# schem.net
KiCad netlist of a schematic drawn in EasyEDA
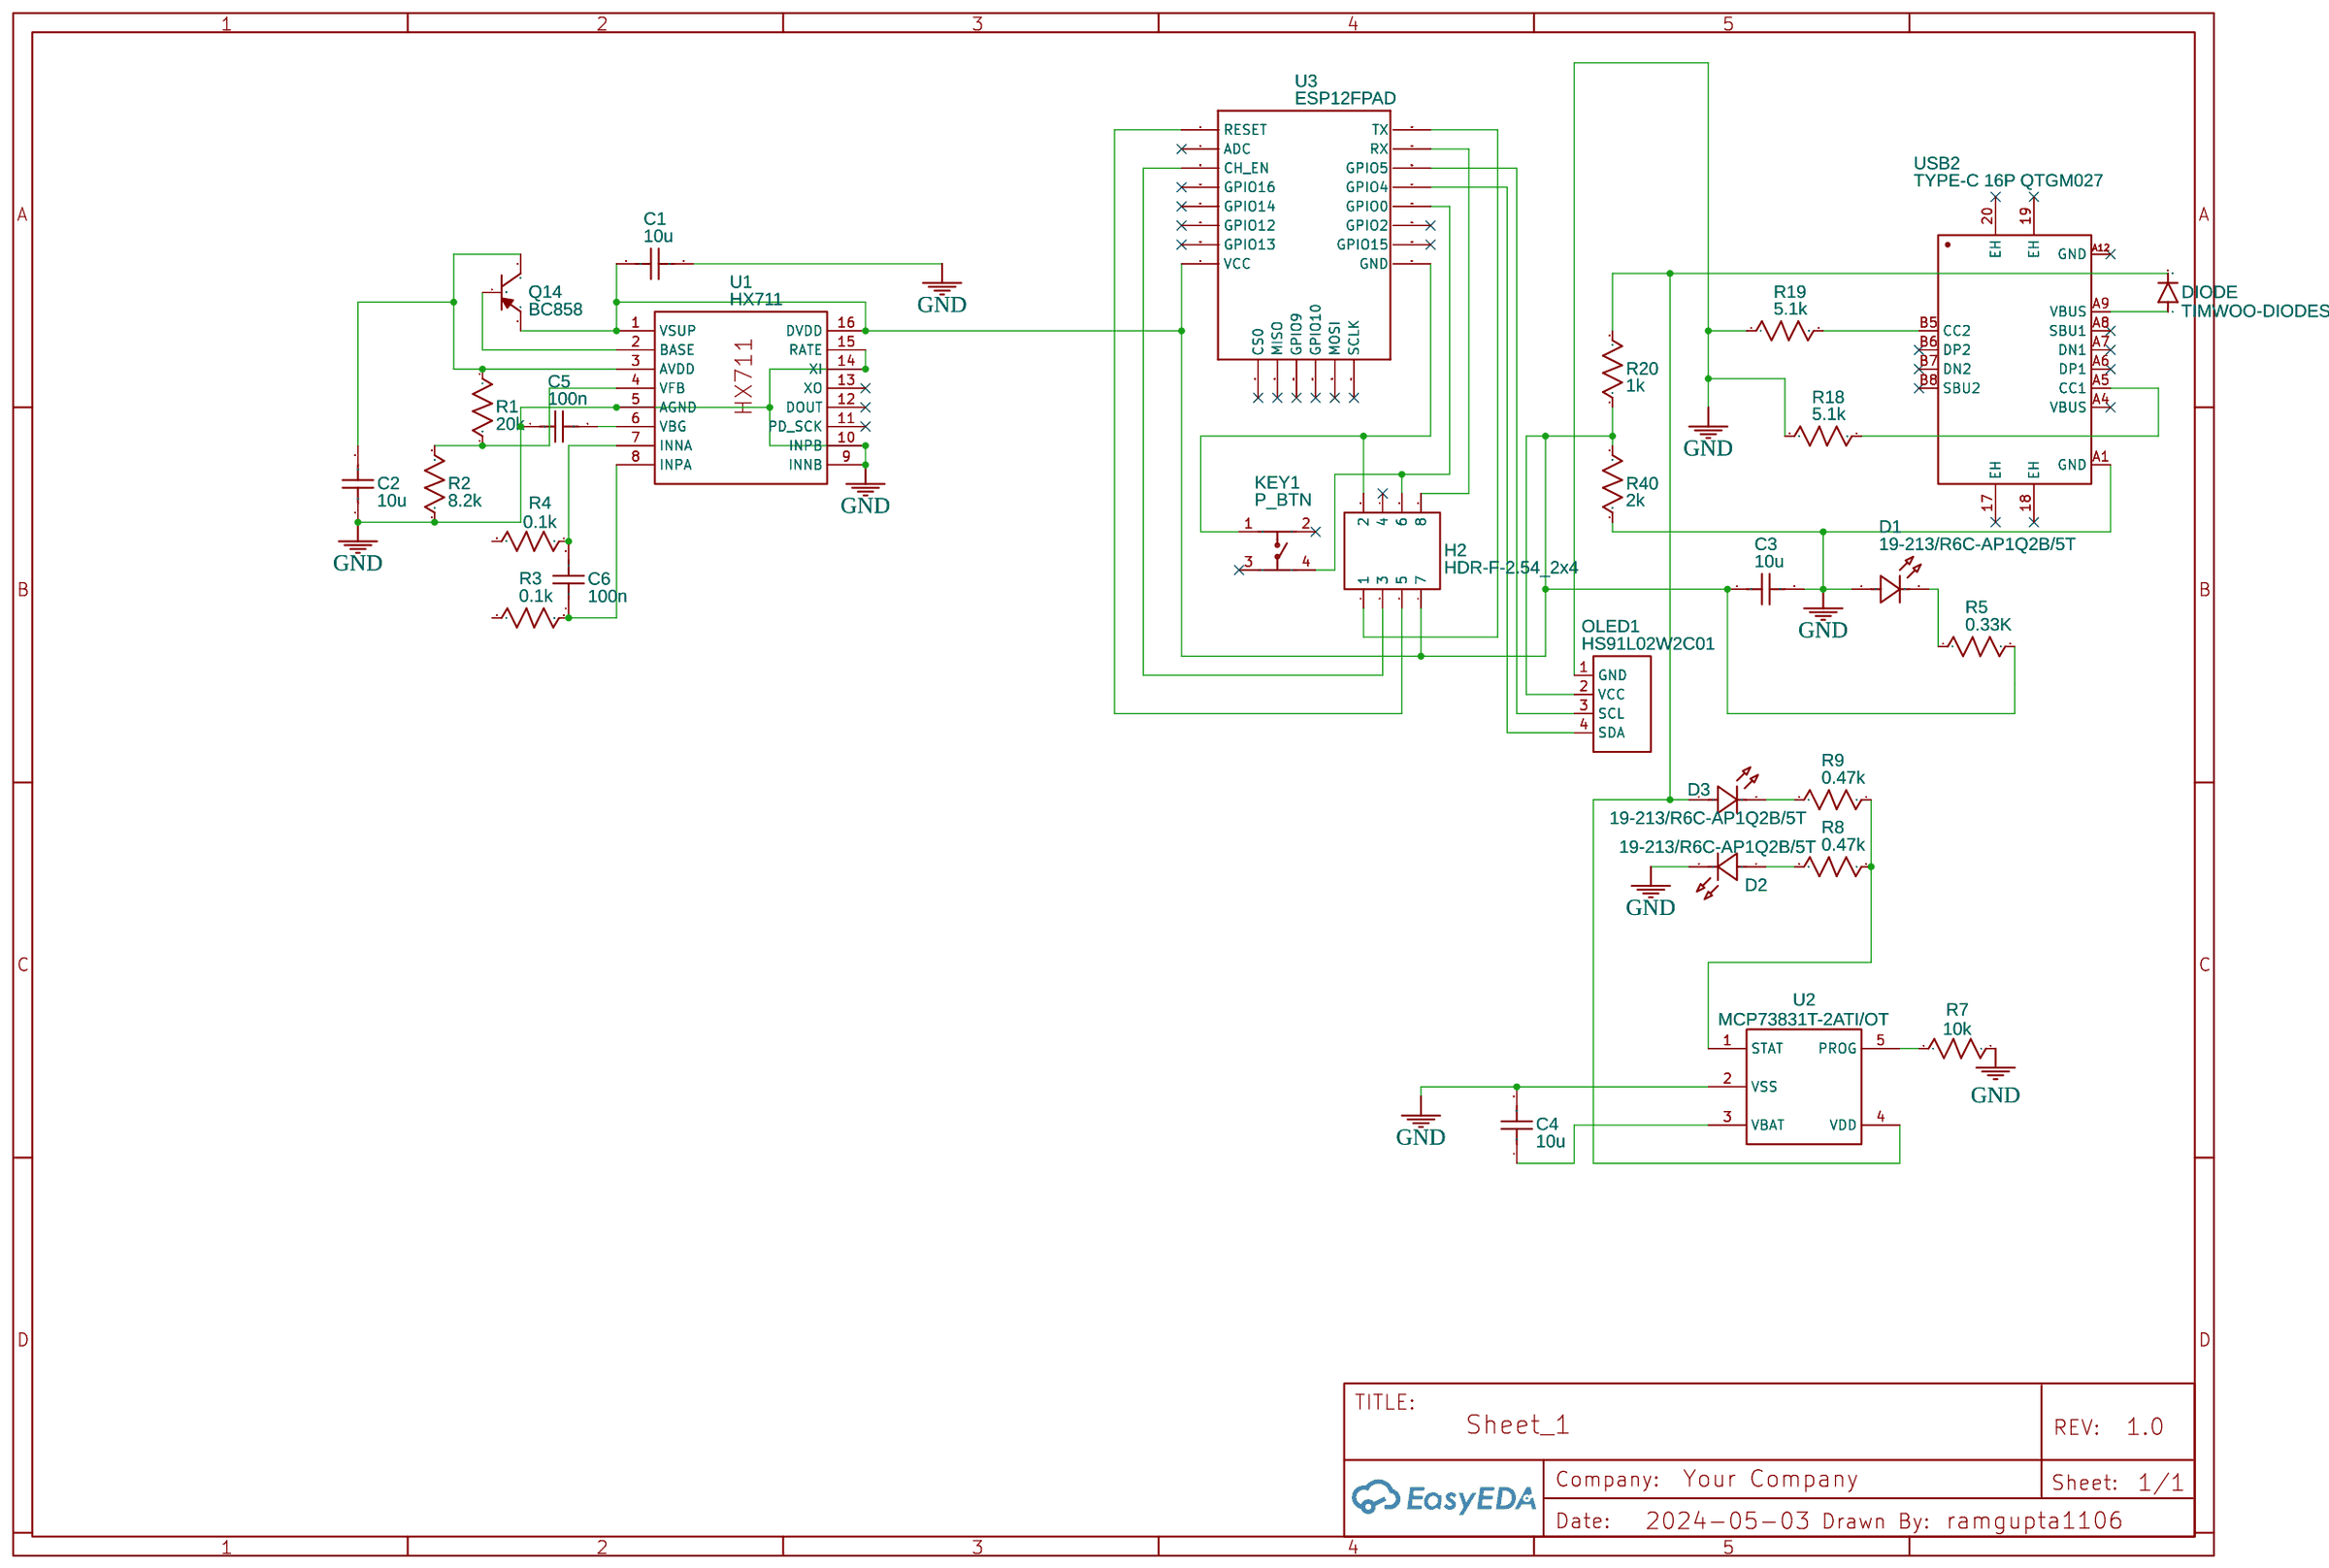
[diagram p0: schematic sheet]

(export (version "E")
  (design (tool "Eeschema 10.0.6"))
  (components
    (comp (ref "C1") (value "10u") (libsource (lib "") (part "C_0603_US")))
    (comp (ref "C2") (value "10u") (libsource (lib "") (part "C_0603_US_1")))
    (comp (ref "C3") (value "10u") (libsource (lib "") (part "C_0603_US")))
    (comp (ref "C4") (value "10u") (libsource (lib "") (part "C_0603_US_1")))
    (comp (ref "C5") (value "100n") (libsource (lib "") (part "C_0603_US")))
    (comp (ref "C6") (value "100n") (libsource (lib "") (part "C_0603_US_1")))
    (comp (ref "D1")
      (value "19-213/R6C-AP1Q2B/5T")
      (fields (field (name "Manufacturer") "EVERLIGHT(亿光)"))
      (libsource (lib "") (part "19-213/R6C-AP1Q2B/5T"))
    )
    (comp (ref "D2")
      (value "19-213/R6C-AP1Q2B/5T")
      (fields (field (name "Manufacturer") "EVERLIGHT(亿光)"))
      (libsource (lib "") (part "19-213/R6C-AP1Q2B/5T_1"))
    )
    (comp (ref "D3")
      (value "19-213/R6C-AP1Q2B/5T")
      (fields (field (name "Manufacturer") "EVERLIGHT(亿光)"))
      (libsource (lib "") (part "19-213/R6C-AP1Q2B/5T"))
    )
    (comp (ref "DIODE") (value "TIMWOO-DIODES_DIODEHV") (libsource (lib "") (part "TIMWOO-DIODES_DIODEHV")))
    (comp (ref "H2") (value "HDR-F-2.54_2x4") (libsource (lib "") (part "HDR-F-2.54_2x4")))
    (comp (ref "KEY1")
      (value "P_BTN")
      (fields (field (name "Manufacturer Part") "4pinTACTPCBTHTPushButton"))
      (libsource (lib "") (part "4PINTACTPCBTHTPUSHBUTTON"))
    )
    (comp (ref "OLED1")
      (value "HS91L02W2C01")
      (fields (field (name "Manufacturer") "HS(汉昇)"))
      (libsource (lib "") (part "HS91L02W2C01"))
    )
    (comp (ref "Q14")
      (value "BC858")
      (fields (field (name "Manufacturer") "HT(Shenzhen Jinyu Semicon)"))
      (libsource (lib "") (part "BC858"))
    )
    (comp (ref "R1") (value "20k") (libsource (lib "") (part "R_0603_US_3")))
    (comp (ref "R2") (value "8.2k") (libsource (lib "") (part "R_0603_US_1")))
    (comp (ref "R3") (value "0.1k") (libsource (lib "") (part "R_0603_US")))
    (comp (ref "R4") (value "0.1k") (libsource (lib "") (part "R_0603_US_2")))
    (comp (ref "R5") (value "0.33K") (libsource (lib "") (part "R_0603_US")))
    (comp (ref "R7") (value "10k") (libsource (lib "") (part "R_0603_US")))
    (comp (ref "R8") (value "0.47k") (libsource (lib "") (part "R_0603_US")))
    (comp (ref "R9") (value "0.47k") (libsource (lib "") (part "R_0603_US")))
    (comp (ref "R18") (value "5.1k") (libsource (lib "") (part "R_0603_US")))
    (comp (ref "R19") (value "5.1k") (libsource (lib "") (part "R_0603_US")))
    (comp (ref "R20") (value "1k") (libsource (lib "") (part "R_0603_US_1")))
    (comp (ref "R40") (value "2k") (libsource (lib "") (part "R_0603_US_1")))
    (comp (ref "U1")
      (value "HX711")
      (fields (field (name "Manufacturer") "AVIA(海芯科技)"))
      (libsource (lib "") (part "HX711"))
    )
    (comp (ref "U2")
      (value "MCP73831T-2ATI/OT")
      (fields (field (name "Manufacturer") "MICROCHIP(美国微芯)"))
      (libsource (lib "") (part "MCP73831T-2ATI/OT"))
    )
    (comp (ref "U3") (value "ESP12FPAD") (libsource (lib "") (part "ESP12FPAD")))
    (comp (ref "USB2")
      (value "TYPE-C 16P QTGM027")
      (fields (field (name "Manufacturer") "SHOU HAN(首韩)"))
      (libsource (lib "") (part "TYPE-C 16P QTGM027"))
    )
  )
  (nets
    (net (code "1") (name "GND") (class "Default")
      (node (ref "C1") (pin "2") (pinfunction "2_2") (pintype "unspecified"))
      (node (ref "C2") (pin "1") (pinfunction "1_1") (pintype "unspecified"))
      (node (ref "C3") (pin "2") (pinfunction "2_2") (pintype "unspecified"))
      (node (ref "C4") (pin "2") (pinfunction "2_2") (pintype "unspecified"))
      (node (ref "C5") (pin "1") (pinfunction "1_1") (pintype "unspecified"))
      (node (ref "D1") (pin "1") (pinfunction "A_1") (pintype "unspecified"))
      (node (ref "D2") (pin "2") (pinfunction "K_2") (pintype "unspecified"))
      (node (ref "OLED1") (pin "1") (pinfunction "GND_1") (pintype "unspecified"))
      (node (ref "R18") (pin "1") (pinfunction "1_1") (pintype "unspecified"))
      (node (ref "R19") (pin "1") (pinfunction "1_1") (pintype "unspecified"))
      (node (ref "R2") (pin "1") (pinfunction "1_1") (pintype "unspecified"))
      (node (ref "R40") (pin "1") (pinfunction "1_1") (pintype "unspecified"))
      (node (ref "R7") (pin "2") (pinfunction "2_2") (pintype "unspecified"))
      (node (ref "U1") (pin "10") (pinfunction "INPB_10") (pintype "unspecified"))
      (node (ref "U1") (pin "14") (pinfunction "XI_14") (pintype "unspecified"))
      (node (ref "U1") (pin "15") (pinfunction "RATE_15") (pintype "unspecified"))
      (node (ref "U1") (pin "5") (pinfunction "AGND_5") (pintype "unspecified"))
      (node (ref "U1") (pin "9") (pinfunction "INNB_9") (pintype "unspecified"))
      (node (ref "U2") (pin "2") (pinfunction "VSS_2") (pintype "unspecified"))
      (node (ref "USB2") (pin "A1") (pinfunction "GND_A1") (pintype "unspecified"))
    )
    (net (code "2") (name "Net-(D1-K)") (class "Default")
      (node (ref "D1") (pin "2") (pinfunction "K_2") (pintype "unspecified"))
      (node (ref "R5") (pin "1") (pinfunction "1_1") (pintype "unspecified"))
    )
    (net (code "3") (name "Net-(D2-A)") (class "Default")
      (node (ref "D2") (pin "1") (pinfunction "A_1") (pintype "unspecified"))
      (node (ref "R8") (pin "1") (pinfunction "1_1") (pintype "unspecified"))
    )
    (net (code "4") (name "Net-(D3-A)") (class "Default")
      (node (ref "D3") (pin "1") (pinfunction "A_1") (pintype "unspecified"))
      (node (ref "DIODE") (pin "C") (pinfunction "C_C") (pintype "bidirectional"))
      (node (ref "R20") (pin "2") (pinfunction "2_2") (pintype "unspecified"))
      (node (ref "U2") (pin "4") (pinfunction "VDD_4") (pintype "unspecified"))
    )
    (net (code "5") (name "Net-(D3-K)") (class "Default")
      (node (ref "D3") (pin "2") (pinfunction "K_2") (pintype "unspecified"))
      (node (ref "R9") (pin "1") (pinfunction "1_1") (pintype "unspecified"))
    )
    (net (code "6") (name "Net-(DIODE-PadA)") (class "Default")
      (node (ref "DIODE") (pin "A") (pinfunction "A_A") (pintype "bidirectional"))
      (node (ref "USB2") (pin "A9") (pinfunction "VBUS_A9") (pintype "unspecified"))
    )
    (net (code "7") (name "Net-(H2-Pad2)") (class "Default")
      (node (ref "H2") (pin "2") (pinfunction "2_2") (pintype "unspecified"))
      (node (ref "KEY1") (pin "1") (pinfunction "1_1") (pintype "unspecified"))
      (node (ref "U3") (pin "GND") (pinfunction "GND_GND") (pintype "bidirectional"))
    )
    (net (code "8") (name "Net-(H2-Pad5)") (class "Default")
      (node (ref "H2") (pin "5") (pinfunction "5_5") (pintype "unspecified"))
      (node (ref "U3") (pin "RESET") (pinfunction "RESET_RESET") (pintype "bidirectional"))
    )
    (net (code "9") (name "Net-(H2-Pad6)") (class "Default")
      (node (ref "H2") (pin "6") (pinfunction "6_6") (pintype "unspecified"))
      (node (ref "KEY1") (pin "4") (pinfunction "4_4") (pintype "unspecified"))
      (node (ref "U3") (pin "GPIO0") (pinfunction "GPIO0_GPIO0") (pintype "bidirectional"))
    )
    (net (code "10") (name "Net-(OLED1-SCL)") (class "Default")
      (node (ref "OLED1") (pin "3") (pinfunction "SCL_3") (pintype "unspecified"))
      (node (ref "U3") (pin "GPIO5") (pinfunction "GPIO5_GPIO5") (pintype "bidirectional"))
    )
    (net (code "11") (name "Net-(OLED1-SDA)") (class "Default")
      (node (ref "OLED1") (pin "4") (pinfunction "SDA_4") (pintype "unspecified"))
      (node (ref "U3") (pin "GPIO4") (pinfunction "GPIO4_GPIO4") (pintype "bidirectional"))
    )
    (net (code "12") (name "Net-(OLED1-VCC)") (class "Default")
      (node (ref "C1") (pin "1") (pinfunction "1_1") (pintype "unspecified"))
      (node (ref "C3") (pin "1") (pinfunction "1_1") (pintype "unspecified"))
      (node (ref "H2") (pin "7") (pinfunction "7_7") (pintype "unspecified"))
      (node (ref "OLED1") (pin "2") (pinfunction "VCC_2") (pintype "unspecified"))
      (node (ref "Q14") (pin "2") (pinfunction "E_2") (pintype "input"))
      (node (ref "R20") (pin "1") (pinfunction "1_1") (pintype "unspecified"))
      (node (ref "R40") (pin "2") (pinfunction "2_2") (pintype "unspecified"))
      (node (ref "R5") (pin "2") (pinfunction "2_2") (pintype "unspecified"))
      (node (ref "U1") (pin "1") (pinfunction "VSUP_1") (pintype "unspecified"))
      (node (ref "U1") (pin "16") (pinfunction "DVDD_16") (pintype "unspecified"))
      (node (ref "U3") (pin "VCC") (pinfunction "VCC_VCC") (pintype "bidirectional"))
    )
    (net (code "13") (name "Net-(Q14-B)") (class "Default")
      (node (ref "Q14") (pin "1") (pinfunction "B_1") (pintype "input"))
      (node (ref "U1") (pin "2") (pinfunction "BASE_2") (pintype "unspecified"))
    )
    (net (code "14") (name "Net-(Q14-C)") (class "Default")
      (node (ref "C2") (pin "2") (pinfunction "2_2") (pintype "unspecified"))
      (node (ref "Q14") (pin "3") (pinfunction "C_3") (pintype "input"))
      (node (ref "R1") (pin "1") (pinfunction "1_1") (pintype "unspecified"))
      (node (ref "U1") (pin "3") (pinfunction "AVDD_3") (pintype "unspecified"))
    )
    (net (code "15") (name "Net-(U1-INNA)") (class "Default")
      (node (ref "C6") (pin "2") (pinfunction "2_2") (pintype "unspecified"))
      (node (ref "R4") (pin "1") (pinfunction "1_1") (pintype "unspecified"))
      (node (ref "U1") (pin "7") (pinfunction "INNA_7") (pintype "unspecified"))
    )
    (net (code "16") (name "Net-(U1-INPA)") (class "Default")
      (node (ref "C6") (pin "1") (pinfunction "1_1") (pintype "unspecified"))
      (node (ref "R3") (pin "2") (pinfunction "2_2") (pintype "unspecified"))
      (node (ref "U1") (pin "8") (pinfunction "INPA_8") (pintype "unspecified"))
    )
    (net (code "17") (name "Net-(U1-VBG)") (class "Default")
      (node (ref "C5") (pin "2") (pinfunction "2_2") (pintype "unspecified"))
      (node (ref "U1") (pin "6") (pinfunction "VBG_6") (pintype "unspecified"))
    )
    (net (code "18") (name "Net-(U1-VFB)") (class "Default")
      (node (ref "R1") (pin "2") (pinfunction "2_2") (pintype "unspecified"))
      (node (ref "R2") (pin "2") (pinfunction "2_2") (pintype "unspecified"))
      (node (ref "U1") (pin "4") (pinfunction "VFB_4") (pintype "unspecified"))
    )
    (net (code "19") (name "Net-(U2-PROG)") (class "Default")
      (node (ref "R7") (pin "1") (pinfunction "1_1") (pintype "unspecified"))
      (node (ref "U2") (pin "5") (pinfunction "PROG_5") (pintype "unspecified"))
    )
    (net (code "20") (name "Net-(U2-STAT)") (class "Default")
      (node (ref "R8") (pin "2") (pinfunction "2_2") (pintype "unspecified"))
      (node (ref "R9") (pin "2") (pinfunction "2_2") (pintype "unspecified"))
      (node (ref "U2") (pin "1") (pinfunction "STAT_1") (pintype "unspecified"))
    )
    (net (code "21") (name "Net-(U2-VBAT)") (class "Default")
      (node (ref "C4") (pin "1") (pinfunction "1_1") (pintype "unspecified"))
      (node (ref "U2") (pin "3") (pinfunction "VBAT_3") (pintype "unspecified"))
    )
    (net (code "22") (name "Net-(U3-CH_EN)") (class "Default")
      (node (ref "H2") (pin "3") (pinfunction "3_3") (pintype "unspecified"))
      (node (ref "U3") (pin "CH_PD") (pinfunction "CH_EN_CH_PD") (pintype "bidirectional"))
    )
    (net (code "23") (name "Net-(U3-RX)") (class "Default")
      (node (ref "H2") (pin "8") (pinfunction "8_8") (pintype "unspecified"))
      (node (ref "U3") (pin "RXD0") (pinfunction "RX_RXD0") (pintype "bidirectional"))
    )
    (net (code "24") (name "Net-(U3-TX)") (class "Default")
      (node (ref "H2") (pin "1") (pinfunction "1_1") (pintype "unspecified"))
      (node (ref "U3") (pin "TXD0") (pinfunction "TX_TXD0") (pintype "bidirectional"))
    )
    (net (code "25") (name "Net-(USB2-CC1)") (class "Default")
      (node (ref "R18") (pin "2") (pinfunction "2_2") (pintype "unspecified"))
      (node (ref "USB2") (pin "A5") (pinfunction "CC1_A5") (pintype "unspecified"))
    )
    (net (code "26") (name "Net-(USB2-CC2)") (class "Default")
      (node (ref "R19") (pin "2") (pinfunction "2_2") (pintype "unspecified"))
      (node (ref "USB2") (pin "B5") (pinfunction "CC2_B5") (pintype "unspecified"))
    )
    (net (code "27") (name "unconnected-(H2-Pad4)") (class "Default")
      (node (ref "H2") (pin "4") (pinfunction "4_4") (pintype "unspecified+no_connect"))
    )
    (net (code "28") (name "unconnected-(KEY1-Pad2)") (class "Default")
      (node (ref "KEY1") (pin "2") (pinfunction "2_2") (pintype "unspecified+no_connect"))
    )
    (net (code "29") (name "unconnected-(KEY1-Pad3)") (class "Default")
      (node (ref "KEY1") (pin "3") (pinfunction "3_3") (pintype "unspecified+no_connect"))
    )
    (net (code "30") (name "unconnected-(R3-Pad1)") (class "Default")
      (node (ref "R3") (pin "1") (pinfunction "1_1") (pintype "unspecified"))
    )
    (net (code "31") (name "unconnected-(R4-Pad2)") (class "Default")
      (node (ref "R4") (pin "2") (pinfunction "2_2") (pintype "unspecified"))
    )
    (net (code "32") (name "unconnected-(U1-DOUT-Pad12)") (class "Default")
      (node (ref "U1") (pin "12") (pinfunction "DOUT_12") (pintype "unspecified+no_connect"))
    )
    (net (code "33") (name "unconnected-(U1-PD_SCK-Pad11)") (class "Default")
      (node (ref "U1") (pin "11") (pinfunction "PD_SCK_11") (pintype "unspecified+no_connect"))
    )
    (net (code "34") (name "unconnected-(U1-XO-Pad13)") (class "Default")
      (node (ref "U1") (pin "13") (pinfunction "XO_13") (pintype "unspecified+no_connect"))
    )
    (net (code "35") (name "unconnected-(U3-PadADC)") (class "Default")
      (node (ref "U3") (pin "ADC") (pinfunction "ADC_ADC") (pintype "bidirectional+no_connect"))
    )
    (net (code "36") (name "unconnected-(U3-PadCS0)") (class "Default")
      (node (ref "U3") (pin "CS0") (pinfunction "CS0_CS0") (pintype "bidirectional+no_connect"))
    )
    (net (code "37") (name "unconnected-(U3-PadGPIO2)") (class "Default")
      (node (ref "U3") (pin "GPIO2") (pinfunction "GPIO2_GPIO2") (pintype "bidirectional+no_connect"))
    )
    (net (code "38") (name "unconnected-(U3-PadGPIO9)") (class "Default")
      (node (ref "U3") (pin "GPIO9") (pinfunction "GPIO9_GPIO9") (pintype "bidirectional+no_connect"))
    )
    (net (code "39") (name "unconnected-(U3-PadGPIO10)") (class "Default")
      (node (ref "U3") (pin "GPIO10") (pinfunction "GPIO10_GPIO10") (pintype "bidirectional+no_connect"))
    )
    (net (code "40") (name "unconnected-(U3-PadGPIO12)") (class "Default")
      (node (ref "U3") (pin "GPIO12") (pinfunction "GPIO12_GPIO12") (pintype "bidirectional+no_connect"))
    )
    (net (code "41") (name "unconnected-(U3-PadGPIO13)") (class "Default")
      (node (ref "U3") (pin "GPIO13") (pinfunction "GPIO13_GPIO13") (pintype "bidirectional+no_connect"))
    )
    (net (code "42") (name "unconnected-(U3-PadGPIO14)") (class "Default")
      (node (ref "U3") (pin "GPIO14") (pinfunction "GPIO14_GPIO14") (pintype "bidirectional+no_connect"))
    )
    (net (code "43") (name "unconnected-(U3-PadGPIO15)") (class "Default")
      (node (ref "U3") (pin "GPIO15") (pinfunction "GPIO15_GPIO15") (pintype "bidirectional+no_connect"))
    )
    (net (code "44") (name "unconnected-(U3-PadGPIO16)") (class "Default")
      (node (ref "U3") (pin "GPIO16") (pinfunction "GPIO16_GPIO16") (pintype "bidirectional+no_connect"))
    )
    (net (code "45") (name "unconnected-(U3-PadMISO)") (class "Default")
      (node (ref "U3") (pin "MISO") (pinfunction "MISO_MISO") (pintype "bidirectional+no_connect"))
    )
    (net (code "46") (name "unconnected-(U3-PadMOSI)") (class "Default")
      (node (ref "U3") (pin "MOSI") (pinfunction "MOSI_MOSI") (pintype "bidirectional+no_connect"))
    )
    (net (code "47") (name "unconnected-(U3-PadSCLK)") (class "Default")
      (node (ref "U3") (pin "SCLK") (pinfunction "SCLK_SCLK") (pintype "bidirectional+no_connect"))
    )
    (net (code "48") (name "unconnected-(USB2-DN1-PadA7)") (class "Default")
      (node (ref "USB2") (pin "A7") (pinfunction "DN1_A7") (pintype "unspecified+no_connect"))
    )
    (net (code "49") (name "unconnected-(USB2-DN2-PadB7)") (class "Default")
      (node (ref "USB2") (pin "B7") (pinfunction "DN2_B7") (pintype "unspecified+no_connect"))
    )
    (net (code "50") (name "unconnected-(USB2-DP1-PadA6)") (class "Default")
      (node (ref "USB2") (pin "A6") (pinfunction "DP1_A6") (pintype "unspecified+no_connect"))
    )
    (net (code "51") (name "unconnected-(USB2-DP2-PadB6)") (class "Default")
      (node (ref "USB2") (pin "B6") (pinfunction "DP2_B6") (pintype "unspecified+no_connect"))
    )
    (net (code "52") (name "unconnected-(USB2-EH-Pad17)") (class "Default")
      (node (ref "USB2") (pin "17") (pinfunction "EH_17") (pintype "unspecified+no_connect"))
    )
    (net (code "53") (name "unconnected-(USB2-EH-Pad18)") (class "Default")
      (node (ref "USB2") (pin "18") (pinfunction "EH_18") (pintype "unspecified+no_connect"))
    )
    (net (code "54") (name "unconnected-(USB2-EH-Pad19)") (class "Default")
      (node (ref "USB2") (pin "19") (pinfunction "EH_19") (pintype "unspecified+no_connect"))
    )
    (net (code "55") (name "unconnected-(USB2-EH-Pad20)") (class "Default")
      (node (ref "USB2") (pin "20") (pinfunction "EH_20") (pintype "unspecified+no_connect"))
    )
    (net (code "56") (name "unconnected-(USB2-GND-PadA12)") (class "Default")
      (node (ref "USB2") (pin "A12") (pinfunction "GND_A12") (pintype "unspecified+no_connect"))
    )
    (net (code "57") (name "unconnected-(USB2-SBU1-PadA8)") (class "Default")
      (node (ref "USB2") (pin "A8") (pinfunction "SBU1_A8") (pintype "unspecified+no_connect"))
    )
    (net (code "58") (name "unconnected-(USB2-SBU2-PadB8)") (class "Default")
      (node (ref "USB2") (pin "B8") (pinfunction "SBU2_B8") (pintype "unspecified+no_connect"))
    )
    (net (code "59") (name "unconnected-(USB2-VBUS-PadA4)") (class "Default")
      (node (ref "USB2") (pin "A4") (pinfunction "VBUS_A4") (pintype "unspecified+no_connect"))
    )
  )
)
